# heater_control.net
KiCad netlist of a schematic drawn in Altium Designer
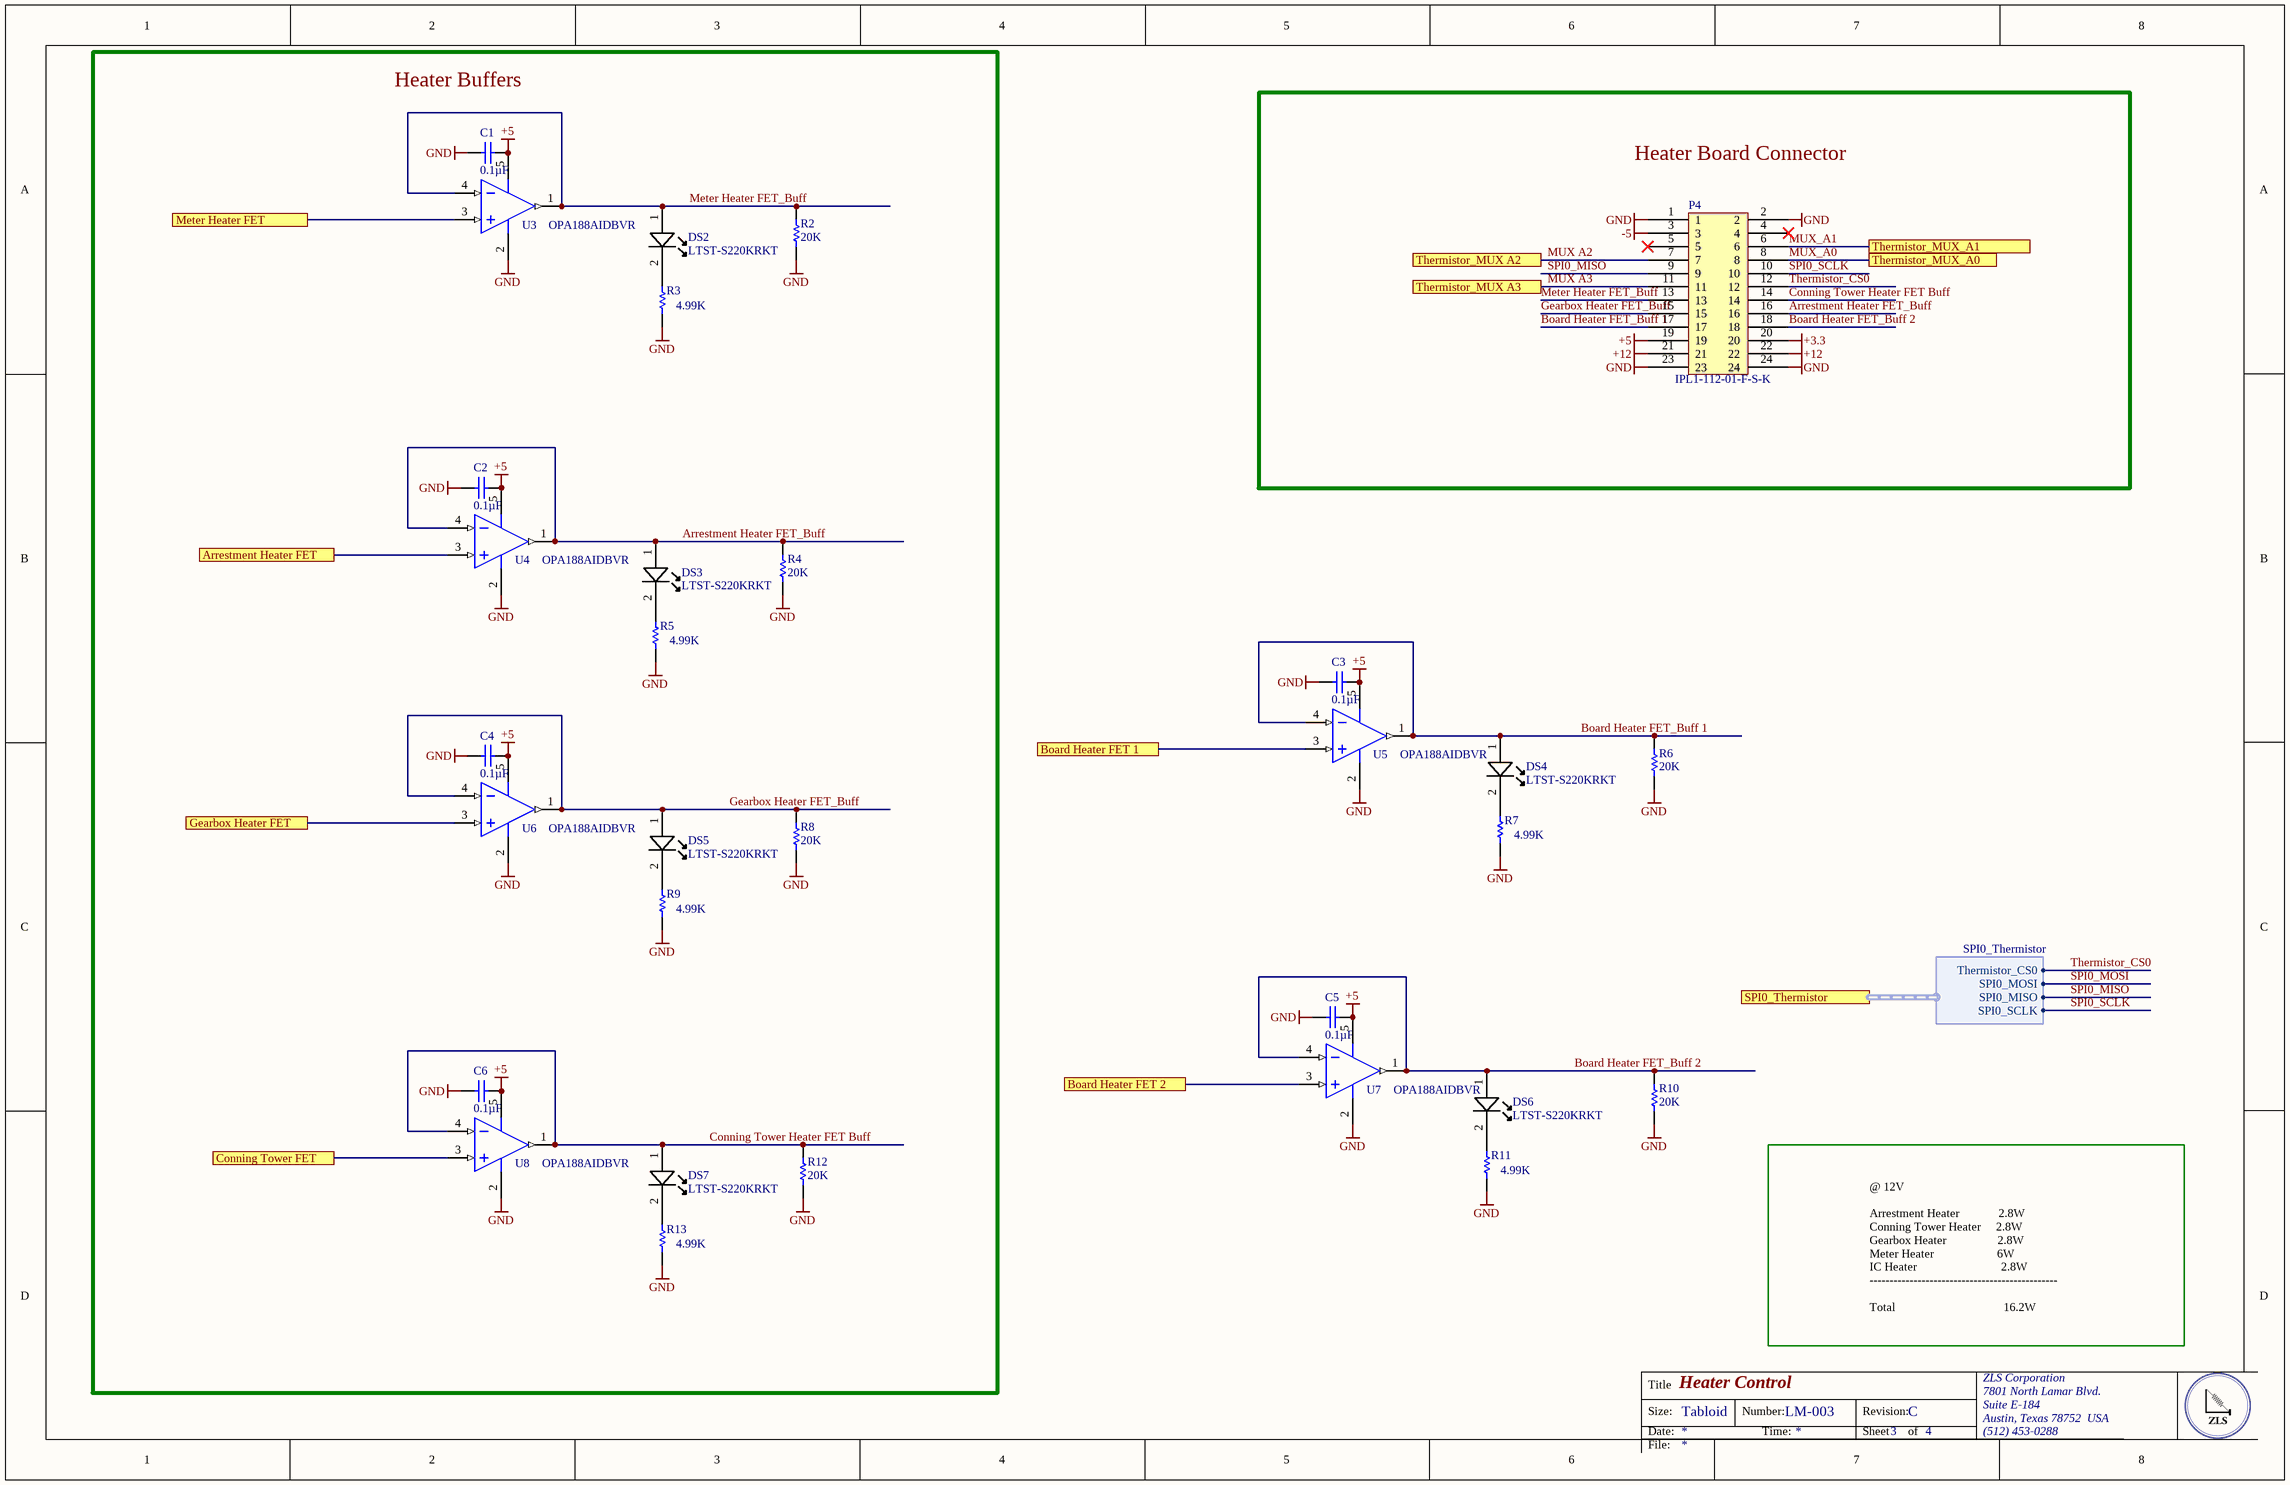
[diagram p0: heater_control.SchDoc]

(export (version "E")
  (design (tool "Eeschema 10.0.6"))
  (components
    (comp (ref "C1")
      (value "CAP CER 0.1UF 25V X7R 0805")
      (footprint "CAPC0805(2012)145_N")
      (fields
        (field (name "MANUFACTURER") "Murata Electronics North America")
        (field (name "MANUFACTURER PART NUMBER") "GRM21BR71E104KA01L")
        (field (name "CAPACITANCE") "0.1µF")
        (field (name "TOLERANCE") "±10%")
      )
      (libsource (lib "Altium Content Vault") (part "CMP-1036-04795-1"))
    )
    (comp (ref "C2")
      (value "CAP CER 0.1UF 25V X7R 0805")
      (footprint "CAPC0805(2012)145_N")
      (fields
        (field (name "MANUFACTURER") "Murata Electronics North America")
        (field (name "MANUFACTURER PART NUMBER") "GRM21BR71E104KA01L")
        (field (name "CAPACITANCE") "0.1µF")
        (field (name "TOLERANCE") "±10%")
      )
      (libsource (lib "Altium Content Vault") (part "CMP-1036-04795-1"))
    )
    (comp (ref "C3")
      (value "CAP CER 0.1UF 25V X7R 0805")
      (footprint "CAPC0805(2012)145_N")
      (fields
        (field (name "MANUFACTURER") "Murata Electronics North America")
        (field (name "MANUFACTURER PART NUMBER") "GRM21BR71E104KA01L")
        (field (name "CAPACITANCE") "0.1µF")
        (field (name "TOLERANCE") "±10%")
      )
      (libsource (lib "Altium Content Vault") (part "CMP-1036-04795-1"))
    )
    (comp (ref "C4")
      (value "CAP CER 0.1UF 25V X7R 0805")
      (footprint "CAPC0805(2012)145_N")
      (fields
        (field (name "MANUFACTURER") "Murata Electronics North America")
        (field (name "MANUFACTURER PART NUMBER") "GRM21BR71E104KA01L")
        (field (name "CAPACITANCE") "0.1µF")
        (field (name "TOLERANCE") "±10%")
      )
      (libsource (lib "Altium Content Vault") (part "CMP-1036-04795-1"))
    )
    (comp (ref "C5")
      (value "CAP CER 0.1UF 25V X7R 0805")
      (footprint "CAPC0805(2012)145_N")
      (fields
        (field (name "MANUFACTURER") "Murata Electronics North America")
        (field (name "MANUFACTURER PART NUMBER") "GRM21BR71E104KA01L")
        (field (name "CAPACITANCE") "0.1µF")
        (field (name "TOLERANCE") "±10%")
      )
      (libsource (lib "Altium Content Vault") (part "CMP-1036-04795-1"))
    )
    (comp (ref "C6")
      (value "CAP CER 0.1UF 25V X7R 0805")
      (footprint "CAPC0805(2012)145_N")
      (fields
        (field (name "MANUFACTURER") "Murata Electronics North America")
        (field (name "MANUFACTURER PART NUMBER") "GRM21BR71E104KA01L")
        (field (name "CAPACITANCE") "0.1µF")
        (field (name "TOLERANCE") "±10%")
      )
      (libsource (lib "Altium Content Vault") (part "CMP-1036-04795-1"))
    )
    (comp (ref "DS2")
      (value "Visible Name Value Type    False Description Lite-On LTST-S220KRKT Red LED, 631 nm 2012 (0805) Side View, Rectangle Lens SMD package STRING")
      (footprint "0805C_L")
      (fields
        (field (name "MANUFACTURER") "Vishay / Lite-On")
        (field (name "MANUFACTURER PART NUMBER") "LTST-S220KRKT")
      )
      (libsource (lib "*") (part "LED A/K"))
    )
    (comp (ref "DS3")
      (value "Visible Name Value Type    False Description Lite-On LTST-S220KRKT Red LED, 631 nm 2012 (0805) Side View, Rectangle Lens SMD package STRING")
      (footprint "0805C_L")
      (fields
        (field (name "MANUFACTURER") "Vishay / Lite-On")
        (field (name "MANUFACTURER PART NUMBER") "LTST-S220KRKT")
      )
      (libsource (lib "*") (part "LED A/K"))
    )
    (comp (ref "DS4")
      (value "Visible Name Value Type    False Description Lite-On LTST-S220KRKT Red LED, 631 nm 2012 (0805) Side View, Rectangle Lens SMD package STRING")
      (footprint "0805C_L")
      (fields
        (field (name "MANUFACTURER") "Vishay / Lite-On")
        (field (name "MANUFACTURER PART NUMBER") "LTST-S220KRKT")
      )
      (libsource (lib "*") (part "LED A/K"))
    )
    (comp (ref "DS5")
      (value "Visible Name Value Type    False Description Lite-On LTST-S220KRKT Red LED, 631 nm 2012 (0805) Side View, Rectangle Lens SMD package STRING")
      (footprint "0805C_L")
      (fields
        (field (name "MANUFACTURER") "Vishay / Lite-On")
        (field (name "MANUFACTURER PART NUMBER") "LTST-S220KRKT")
      )
      (libsource (lib "*") (part "LED A/K"))
    )
    (comp (ref "DS6")
      (value "Visible Name Value Type    False Description Lite-On LTST-S220KRKT Red LED, 631 nm 2012 (0805) Side View, Rectangle Lens SMD package STRING")
      (footprint "0805C_L")
      (fields
        (field (name "MANUFACTURER") "Vishay / Lite-On")
        (field (name "MANUFACTURER PART NUMBER") "LTST-S220KRKT")
      )
      (libsource (lib "*") (part "LED A/K"))
    )
    (comp (ref "DS7")
      (value "Visible Name Value Type    False Description Lite-On LTST-S220KRKT Red LED, 631 nm 2012 (0805) Side View, Rectangle Lens SMD package STRING")
      (footprint "0805C_L")
      (fields
        (field (name "MANUFACTURER") "Vishay / Lite-On")
        (field (name "MANUFACTURER PART NUMBER") "LTST-S220KRKT")
      )
      (libsource (lib "*") (part "LED A/K"))
    )
    (comp (ref "P4")
      (value "IPL1-112-01-F-S-K")
      (footprint "IPL1-112-01-F-S-K")
      (description "IPL1-112-01-F-D-K")
      (fields (field (name "MANUFACTURER") "Samtec Inc."))
      (libsource (lib "ZLS_Schematic_lib") (part "IPL1-112-01-F-S-K"))
    )
    (comp (ref "R2")
      (value "20K")
      (footprint "RESC0805(2012)_L")
      (description "RES SMD 20K OHM 1% 1/8W 0805")
      (fields
        (field (name "MANUFACTURER") "Panasonic Electronic Components")
        (field (name "MANUFACTURER PART NUMBER") "ERJ-6ENF2002V")
      )
      (libsource (lib "Altium Content Vault") (part "CMP-1013-00215-1"))
    )
    (comp (ref "R3")
      (value "4.99K")
      (footprint "RESC0805(2012)_L")
      (description "RES SMD 4.99K OHM 1% 1/8W 0805")
      (fields
        (field (name "MANUFACTURER") "Panasonic Electronic Components")
        (field (name "MANUFACTURER PART NUMBER") "ERJ-6ENF4991V")
      )
      (libsource (lib "Altium Content Vault") (part "CMP-1013-00215-1"))
    )
    (comp (ref "R4")
      (value "20K")
      (footprint "RESC0805(2012)_L")
      (description "RES SMD 20K OHM 1% 1/8W 0805")
      (fields
        (field (name "MANUFACTURER") "Panasonic Electronic Components")
        (field (name "MANUFACTURER PART NUMBER") "ERJ-6ENF2002V")
      )
      (libsource (lib "Altium Content Vault") (part "CMP-1013-00215-1"))
    )
    (comp (ref "R5")
      (value "4.99K")
      (footprint "RESC0805(2012)_L")
      (description "RES SMD 4.99K OHM 1% 1/8W 0805")
      (fields
        (field (name "MANUFACTURER") "Panasonic Electronic Components")
        (field (name "MANUFACTURER PART NUMBER") "ERJ-6ENF4991V")
      )
      (libsource (lib "Altium Content Vault") (part "CMP-1013-00215-1"))
    )
    (comp (ref "R6")
      (value "20K")
      (footprint "RESC0805(2012)_L")
      (description "RES SMD 20K OHM 1% 1/8W 0805")
      (fields
        (field (name "MANUFACTURER") "Panasonic Electronic Components")
        (field (name "MANUFACTURER PART NUMBER") "ERJ-6ENF2002V")
      )
      (libsource (lib "Altium Content Vault") (part "CMP-1013-00215-1"))
    )
    (comp (ref "R7")
      (value "4.99K")
      (footprint "RESC0805(2012)_L")
      (description "RES SMD 4.99K OHM 1% 1/8W 0805")
      (fields
        (field (name "MANUFACTURER") "Panasonic Electronic Components")
        (field (name "MANUFACTURER PART NUMBER") "ERJ-6ENF4991V")
      )
      (libsource (lib "Altium Content Vault") (part "CMP-1013-00215-1"))
    )
    (comp (ref "R8")
      (value "20K")
      (footprint "RESC0805(2012)_L")
      (description "RES SMD 20K OHM 1% 1/8W 0805")
      (fields
        (field (name "MANUFACTURER") "Panasonic Electronic Components")
        (field (name "MANUFACTURER PART NUMBER") "ERJ-6ENF2002V")
      )
      (libsource (lib "Altium Content Vault") (part "CMP-1013-00215-1"))
    )
    (comp (ref "R9")
      (value "4.99K")
      (footprint "RESC0805(2012)_L")
      (description "RES SMD 4.99K OHM 1% 1/8W 0805")
      (fields
        (field (name "MANUFACTURER") "Panasonic Electronic Components")
        (field (name "MANUFACTURER PART NUMBER") "ERJ-6ENF4991V")
      )
      (libsource (lib "Altium Content Vault") (part "CMP-1013-00215-1"))
    )
    (comp (ref "R10")
      (value "20K")
      (footprint "RESC0805(2012)_L")
      (description "RES SMD 20K OHM 1% 1/8W 0805")
      (fields
        (field (name "MANUFACTURER") "Panasonic Electronic Components")
        (field (name "MANUFACTURER PART NUMBER") "ERJ-6ENF2002V")
      )
      (libsource (lib "Altium Content Vault") (part "CMP-1013-00215-1"))
    )
    (comp (ref "R11")
      (value "4.99K")
      (footprint "RESC0805(2012)_L")
      (description "RES SMD 4.99K OHM 1% 1/8W 0805")
      (fields
        (field (name "MANUFACTURER") "Panasonic Electronic Components")
        (field (name "MANUFACTURER PART NUMBER") "ERJ-6ENF4991V")
      )
      (libsource (lib "Altium Content Vault") (part "CMP-1013-00215-1"))
    )
    (comp (ref "R12")
      (value "20K")
      (footprint "RESC0805(2012)_L")
      (description "RES SMD 20K OHM 1% 1/8W 0805")
      (fields
        (field (name "MANUFACTURER") "Panasonic Electronic Components")
        (field (name "MANUFACTURER PART NUMBER") "ERJ-6ENF2002V")
      )
      (libsource (lib "Altium Content Vault") (part "CMP-1013-00215-1"))
    )
    (comp (ref "R13")
      (value "4.99K")
      (footprint "RESC0805(2012)_L")
      (description "RES SMD 4.99K OHM 1% 1/8W 0805")
      (fields
        (field (name "MANUFACTURER") "Panasonic Electronic Components")
        (field (name "MANUFACTURER PART NUMBER") "ERJ-6ENF4991V")
      )
      (libsource (lib "Altium Content Vault") (part "CMP-1013-00215-1"))
    )
    (comp (ref "U3")
      (value "OPA188AIDBVR")
      (footprint "DBV0005A_M")
      (fields (field (name "MANUFACTURER") "Texas Instruments"))
      (libsource (lib "Altium Content Vault") (part "CMP-0809-00005-2"))
    )
    (comp (ref "U4")
      (value "OPA188AIDBVR")
      (footprint "DBV0005A_M")
      (fields (field (name "MANUFACTURER") "Texas Instruments"))
      (libsource (lib "Altium Content Vault") (part "CMP-0809-00005-2"))
    )
    (comp (ref "U5")
      (value "OPA188AIDBVR")
      (footprint "DBV0005A_M")
      (fields (field (name "MANUFACTURER") "Texas Instruments"))
      (libsource (lib "Altium Content Vault") (part "CMP-0809-00005-2"))
    )
    (comp (ref "U6")
      (value "OPA188AIDBVR")
      (footprint "DBV0005A_M")
      (fields (field (name "MANUFACTURER") "Texas Instruments"))
      (libsource (lib "Altium Content Vault") (part "CMP-0809-00005-2"))
    )
    (comp (ref "U7")
      (value "OPA188AIDBVR")
      (footprint "DBV0005A_M")
      (fields (field (name "MANUFACTURER") "Texas Instruments"))
      (libsource (lib "Altium Content Vault") (part "CMP-0809-00005-2"))
    )
    (comp (ref "U8")
      (value "OPA188AIDBVR")
      (footprint "DBV0005A_M")
      (fields (field (name "MANUFACTURER") "Texas Instruments"))
      (libsource (lib "Altium Content Vault") (part "CMP-0809-00005-2"))
    )
  )
  (nets
    (net (code "2") (name "+3.3") (class "Default")
      (node (ref "P4") (pin "20") (pinfunction "20_20") (pintype "passive"))
    )
    (net (code "3") (name "+5") (class "Default")
      (node (ref "C1") (pin "2") (pinfunction "2_2") (pintype "passive"))
      (node (ref "C2") (pin "2") (pinfunction "2_2") (pintype "passive"))
      (node (ref "C3") (pin "2") (pinfunction "2_2") (pintype "passive"))
      (node (ref "C4") (pin "2") (pinfunction "2_2") (pintype "passive"))
      (node (ref "C5") (pin "2") (pinfunction "2_2") (pintype "passive"))
      (node (ref "C6") (pin "2") (pinfunction "2_2") (pintype "passive"))
      (node (ref "P4") (pin "19") (pinfunction "19_19") (pintype "passive"))
      (node (ref "U3") (pin "5") (pinfunction "V+_5") (pintype "power_in"))
      (node (ref "U4") (pin "5") (pinfunction "V+_5") (pintype "power_in"))
      (node (ref "U5") (pin "5") (pinfunction "V+_5") (pintype "power_in"))
      (node (ref "U6") (pin "5") (pinfunction "V+_5") (pintype "power_in"))
      (node (ref "U7") (pin "5") (pinfunction "V+_5") (pintype "power_in"))
      (node (ref "U8") (pin "5") (pinfunction "V+_5") (pintype "power_in"))
    )
    (net (code "4") (name "+12") (class "Default")
      (node (ref "P4") (pin "21") (pinfunction "21_21") (pintype "passive"))
      (node (ref "P4") (pin "22") (pinfunction "22_22") (pintype "passive"))
    )
    (net (code "5") (name "-5") (class "Default")
      (node (ref "P4") (pin "3") (pinfunction "3_3") (pintype "passive"))
    )
    (net (code "6") (name "/Arrestment Heater FET") (class "Default")
      (node (ref "U4") (pin "3") (pinfunction "IN+_3") (pintype "input"))
    )
    (net (code "7") (name "/Arrestment Heater FET_Buff") (class "Default")
      (node (ref "DS3") (pin "1") (pinfunction "A_1") (pintype "passive"))
      (node (ref "P4") (pin "16") (pinfunction "16_16") (pintype "passive"))
      (node (ref "R4") (pin "1") (pinfunction "1_1") (pintype "passive"))
      (node (ref "U4") (pin "1") (pinfunction "OUT_1") (pintype "output"))
      (node (ref "U4") (pin "4") (pinfunction "IN-_4") (pintype "input"))
    )
    (net (code "8") (name "/Board Heater FET 1") (class "Default")
      (node (ref "U5") (pin "3") (pinfunction "IN+_3") (pintype "input"))
    )
    (net (code "9") (name "/Board Heater FET 2") (class "Default")
      (node (ref "U7") (pin "3") (pinfunction "IN+_3") (pintype "input"))
    )
    (net (code "10") (name "/Board Heater FET_Buff 1") (class "Default")
      (node (ref "DS4") (pin "1") (pinfunction "A_1") (pintype "passive"))
      (node (ref "P4") (pin "17") (pinfunction "17_17") (pintype "passive"))
      (node (ref "R6") (pin "1") (pinfunction "1_1") (pintype "passive"))
      (node (ref "U5") (pin "1") (pinfunction "OUT_1") (pintype "output"))
      (node (ref "U5") (pin "4") (pinfunction "IN-_4") (pintype "input"))
    )
    (net (code "11") (name "/Board Heater FET_Buff 2") (class "Default")
      (node (ref "DS6") (pin "1") (pinfunction "A_1") (pintype "passive"))
      (node (ref "P4") (pin "18") (pinfunction "18_18") (pintype "passive"))
      (node (ref "R10") (pin "1") (pinfunction "1_1") (pintype "passive"))
      (node (ref "U7") (pin "1") (pinfunction "OUT_1") (pintype "output"))
      (node (ref "U7") (pin "4") (pinfunction "IN-_4") (pintype "input"))
    )
    (net (code "12") (name "/Conning Tower FET") (class "Default")
      (node (ref "U8") (pin "3") (pinfunction "IN+_3") (pintype "input"))
    )
    (net (code "13") (name "/Conning Tower Heater FET Buff") (class "Default")
      (node (ref "DS7") (pin "1") (pinfunction "A_1") (pintype "passive"))
      (node (ref "P4") (pin "14") (pinfunction "14_14") (pintype "passive"))
      (node (ref "R12") (pin "1") (pinfunction "1_1") (pintype "passive"))
      (node (ref "U8") (pin "1") (pinfunction "OUT_1") (pintype "output"))
      (node (ref "U8") (pin "4") (pinfunction "IN-_4") (pintype "input"))
    )
    (net (code "14") (name "/Gearbox Heater FET") (class "Default")
      (node (ref "U6") (pin "3") (pinfunction "IN+_3") (pintype "input"))
    )
    (net (code "15") (name "/Gearbox Heater FET_Buff") (class "Default")
      (node (ref "DS5") (pin "1") (pinfunction "A_1") (pintype "passive"))
      (node (ref "P4") (pin "15") (pinfunction "15_15") (pintype "passive"))
      (node (ref "R8") (pin "1") (pinfunction "1_1") (pintype "passive"))
      (node (ref "U6") (pin "1") (pinfunction "OUT_1") (pintype "output"))
      (node (ref "U6") (pin "4") (pinfunction "IN-_4") (pintype "input"))
    )
    (net (code "16") (name "/MUX A2") (class "Default")
      (node (ref "P4") (pin "7") (pinfunction "7_7") (pintype "passive"))
    )
    (net (code "17") (name "/MUX A3") (class "Default")
      (node (ref "P4") (pin "11") (pinfunction "11_11") (pintype "passive"))
    )
    (net (code "18") (name "/MUX_A0") (class "Default")
      (node (ref "P4") (pin "8") (pinfunction "8_8") (pintype "passive"))
    )
    (net (code "19") (name "/MUX_A1") (class "Default")
      (node (ref "P4") (pin "6") (pinfunction "6_6") (pintype "passive"))
    )
    (net (code "20") (name "/Meter Heater FET") (class "Default")
      (node (ref "U3") (pin "3") (pinfunction "IN+_3") (pintype "input"))
    )
    (net (code "21") (name "/Meter Heater FET_Buff") (class "Default")
      (node (ref "DS2") (pin "1") (pinfunction "A_1") (pintype "passive"))
      (node (ref "P4") (pin "13") (pinfunction "13_13") (pintype "passive"))
      (node (ref "R2") (pin "1") (pinfunction "1_1") (pintype "passive"))
      (node (ref "U3") (pin "1") (pinfunction "OUT_1") (pintype "output"))
      (node (ref "U3") (pin "4") (pinfunction "IN-_4") (pintype "input"))
    )
    (net (code "22") (name "/SPI0_MISO") (class "Default")
      (node (ref "P4") (pin "9") (pinfunction "9_9") (pintype "passive"))
    )
    (net (code "24") (name "/SPI0_SCLK") (class "Default")
      (node (ref "P4") (pin "10") (pinfunction "10_10") (pintype "passive"))
    )
    (net (code "25") (name "/Thermistor_CS0") (class "Default")
      (node (ref "P4") (pin "12") (pinfunction "12_12") (pintype "passive"))
    )
    (net (code "27") (name "GND") (class "Default")
      (node (ref "C1") (pin "1") (pinfunction "1_1") (pintype "passive"))
      (node (ref "C2") (pin "1") (pinfunction "1_1") (pintype "passive"))
      (node (ref "C3") (pin "1") (pinfunction "1_1") (pintype "passive"))
      (node (ref "C4") (pin "1") (pinfunction "1_1") (pintype "passive"))
      (node (ref "C5") (pin "1") (pinfunction "1_1") (pintype "passive"))
      (node (ref "C6") (pin "1") (pinfunction "1_1") (pintype "passive"))
      (node (ref "P4") (pin "1") (pinfunction "1_1") (pintype "passive"))
      (node (ref "P4") (pin "2") (pinfunction "2_2") (pintype "passive"))
      (node (ref "P4") (pin "23") (pinfunction "23_23") (pintype "passive"))
      (node (ref "P4") (pin "24") (pinfunction "24_24") (pintype "passive"))
      (node (ref "R10") (pin "2") (pinfunction "2_2") (pintype "passive"))
      (node (ref "R11") (pin "2") (pinfunction "2_2") (pintype "passive"))
      (node (ref "R12") (pin "2") (pinfunction "2_2") (pintype "passive"))
      (node (ref "R13") (pin "2") (pinfunction "2_2") (pintype "passive"))
      (node (ref "R2") (pin "2") (pinfunction "2_2") (pintype "passive"))
      (node (ref "R3") (pin "2") (pinfunction "2_2") (pintype "passive"))
      (node (ref "R4") (pin "2") (pinfunction "2_2") (pintype "passive"))
      (node (ref "R5") (pin "2") (pinfunction "2_2") (pintype "passive"))
      (node (ref "R6") (pin "2") (pinfunction "2_2") (pintype "passive"))
      (node (ref "R7") (pin "2") (pinfunction "2_2") (pintype "passive"))
      (node (ref "R8") (pin "2") (pinfunction "2_2") (pintype "passive"))
      (node (ref "R9") (pin "2") (pinfunction "2_2") (pintype "passive"))
      (node (ref "U3") (pin "2") (pinfunction "V-_2") (pintype "power_in"))
      (node (ref "U4") (pin "2") (pinfunction "V-_2") (pintype "power_in"))
      (node (ref "U5") (pin "2") (pinfunction "V-_2") (pintype "power_in"))
      (node (ref "U6") (pin "2") (pinfunction "V-_2") (pintype "power_in"))
      (node (ref "U7") (pin "2") (pinfunction "V-_2") (pintype "power_in"))
      (node (ref "U8") (pin "2") (pinfunction "V-_2") (pintype "power_in"))
    )
    (net (code "28") (name "Net-(DS2-K)") (class "Default")
      (node (ref "DS2") (pin "2") (pinfunction "K_2") (pintype "passive"))
      (node (ref "R3") (pin "1") (pinfunction "1_1") (pintype "passive"))
    )
    (net (code "29") (name "Net-(DS3-K)") (class "Default")
      (node (ref "DS3") (pin "2") (pinfunction "K_2") (pintype "passive"))
      (node (ref "R5") (pin "1") (pinfunction "1_1") (pintype "passive"))
    )
    (net (code "30") (name "Net-(DS4-K)") (class "Default")
      (node (ref "DS4") (pin "2") (pinfunction "K_2") (pintype "passive"))
      (node (ref "R7") (pin "1") (pinfunction "1_1") (pintype "passive"))
    )
    (net (code "31") (name "Net-(DS5-K)") (class "Default")
      (node (ref "DS5") (pin "2") (pinfunction "K_2") (pintype "passive"))
      (node (ref "R9") (pin "1") (pinfunction "1_1") (pintype "passive"))
    )
    (net (code "32") (name "Net-(DS6-K)") (class "Default")
      (node (ref "DS6") (pin "2") (pinfunction "K_2") (pintype "passive"))
      (node (ref "R11") (pin "1") (pinfunction "1_1") (pintype "passive"))
    )
    (net (code "33") (name "Net-(DS7-K)") (class "Default")
      (node (ref "DS7") (pin "2") (pinfunction "K_2") (pintype "passive"))
      (node (ref "R13") (pin "1") (pinfunction "1_1") (pintype "passive"))
    )
    (net (code "34") (name "unconnected-(P4-Pad4)") (class "Default")
      (node (ref "P4") (pin "4") (pinfunction "4_4") (pintype "passive+no_connect"))
    )
    (net (code "35") (name "unconnected-(P4-Pad5)") (class "Default")
      (node (ref "P4") (pin "5") (pinfunction "5_5") (pintype "passive+no_connect"))
    )
  )
)
